# AD_0.net
KiCad netlist of a schematic drawn in Altium Designer
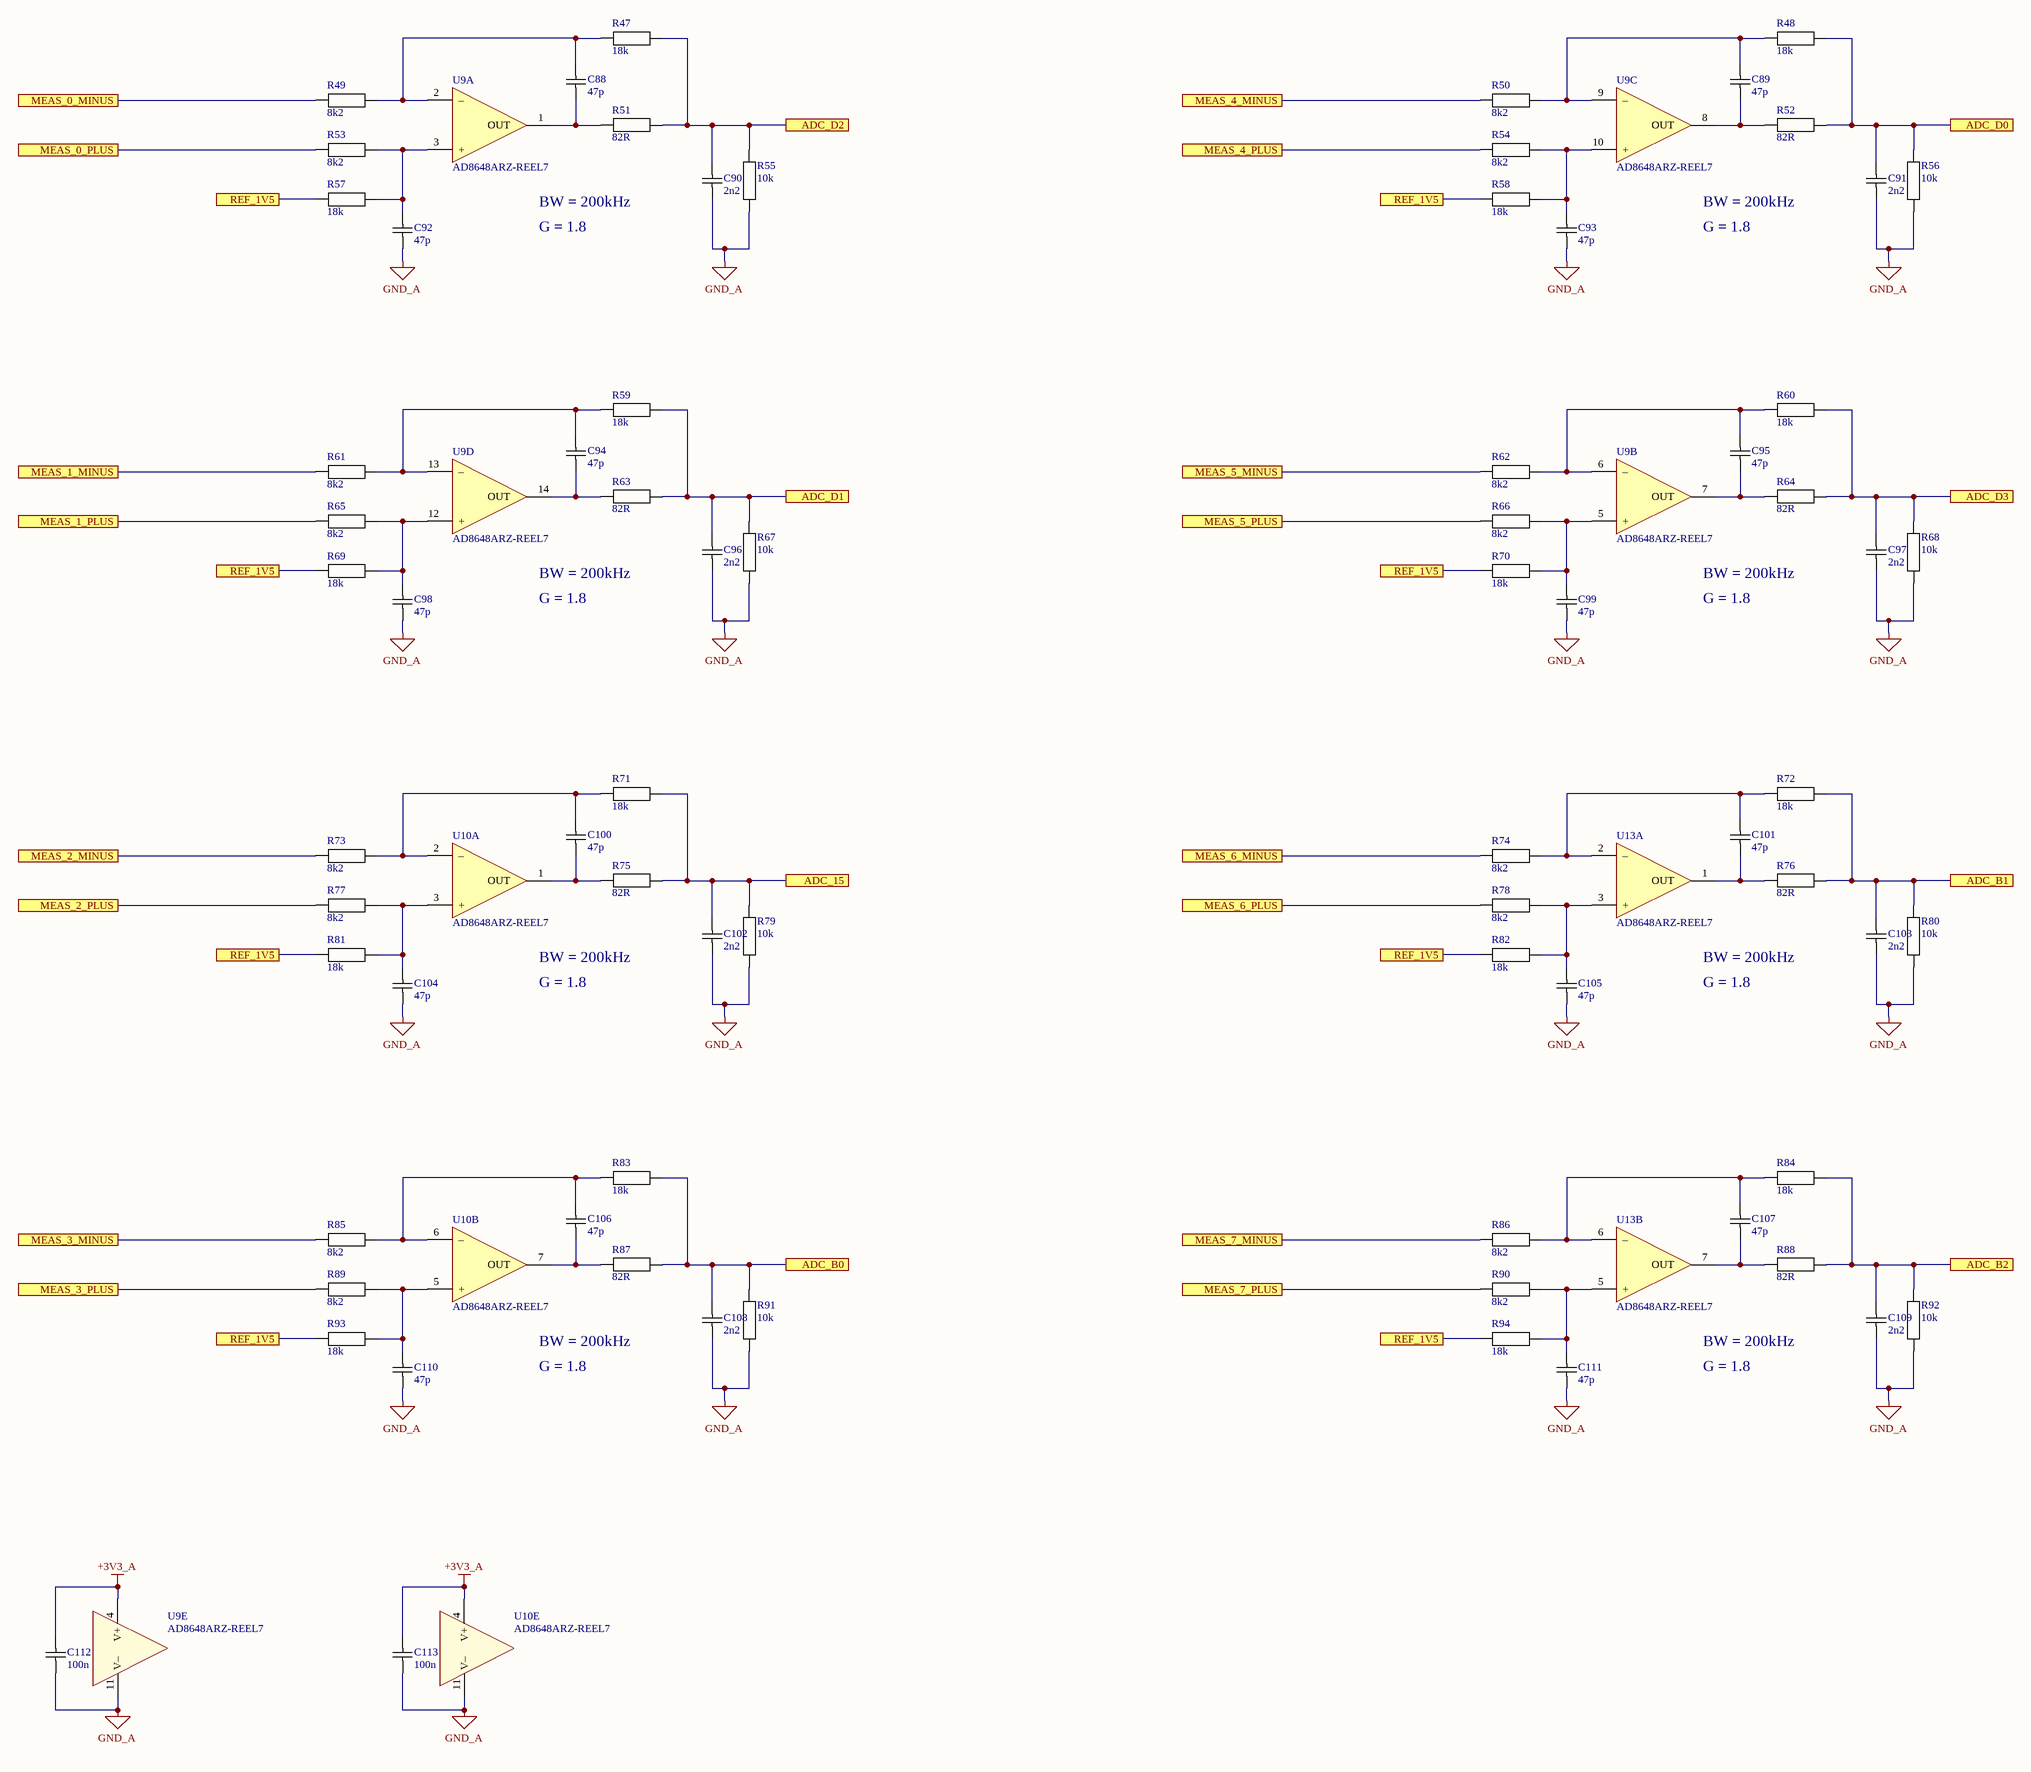
[diagram p0: AD_0.SchDoc]

(export (version "E")
  (design (tool "Eeschema 10.0.6"))
  (components
    (comp (ref "C88")
      (value "47p")
      (footprint "CAPACITOR 1608 REFLOW")
      (description "Capacitor X7R 10% 50V 1608(0603)")
      (libsource (lib "Capacitor") (part "Capacitor"))
    )
    (comp (ref "C89")
      (value "47p")
      (footprint "CAPACITOR 1608 REFLOW")
      (description "Capacitor X7R 10% 50V 1608(0603)")
      (libsource (lib "Capacitor") (part "Capacitor"))
    )
    (comp (ref "C90")
      (value "2n2")
      (footprint "CAPACITOR 1608 REFLOW")
      (description "Capacitor X7R 10% 50V 1608(0603)")
      (libsource (lib "Capacitor") (part "Capacitor"))
    )
    (comp (ref "C91")
      (value "2n2")
      (footprint "CAPACITOR 1608 REFLOW")
      (description "Capacitor X7R 10% 50V 1608(0603)")
      (libsource (lib "Capacitor") (part "Capacitor"))
    )
    (comp (ref "C92")
      (value "47p")
      (footprint "CAPACITOR 1608 REFLOW")
      (description "Capacitor X7R 10% 50V 1608(0603)")
      (libsource (lib "Capacitor") (part "Capacitor"))
    )
    (comp (ref "C93")
      (value "47p")
      (footprint "CAPACITOR 1608 REFLOW")
      (description "Capacitor X7R 10% 50V 1608(0603)")
      (libsource (lib "Capacitor") (part "Capacitor"))
    )
    (comp (ref "C94")
      (value "47p")
      (footprint "CAPACITOR 1608 REFLOW")
      (description "Capacitor X7R 10% 50V 1608(0603)")
      (libsource (lib "Capacitor") (part "Capacitor"))
    )
    (comp (ref "C95")
      (value "47p")
      (footprint "CAPACITOR 1608 REFLOW")
      (description "Capacitor X7R 10% 50V 1608(0603)")
      (libsource (lib "Capacitor") (part "Capacitor"))
    )
    (comp (ref "C96")
      (value "2n2")
      (footprint "CAPACITOR 1608 REFLOW")
      (description "Capacitor X7R 10% 50V 1608(0603)")
      (libsource (lib "Capacitor") (part "Capacitor"))
    )
    (comp (ref "C97")
      (value "2n2")
      (footprint "CAPACITOR 1608 REFLOW")
      (description "Capacitor X7R 10% 50V 1608(0603)")
      (libsource (lib "Capacitor") (part "Capacitor"))
    )
    (comp (ref "C98")
      (value "47p")
      (footprint "CAPACITOR 1608 REFLOW")
      (description "Capacitor X7R 10% 50V 1608(0603)")
      (libsource (lib "Capacitor") (part "Capacitor"))
    )
    (comp (ref "C99")
      (value "47p")
      (footprint "CAPACITOR 1608 REFLOW")
      (description "Capacitor X7R 10% 50V 1608(0603)")
      (libsource (lib "Capacitor") (part "Capacitor"))
    )
    (comp (ref "C100")
      (value "47p")
      (footprint "CAPACITOR 1608 REFLOW")
      (description "Capacitor X7R 10% 50V 1608(0603)")
      (libsource (lib "Capacitor") (part "Capacitor"))
    )
    (comp (ref "C101")
      (value "47p")
      (footprint "CAPACITOR 1608 REFLOW")
      (description "Capacitor X7R 10% 50V 1608(0603)")
      (libsource (lib "Capacitor") (part "Capacitor"))
    )
    (comp (ref "C102")
      (value "2n2")
      (footprint "CAPACITOR 1608 REFLOW")
      (description "Capacitor X7R 10% 50V 1608(0603)")
      (libsource (lib "Capacitor") (part "Capacitor"))
    )
    (comp (ref "C103")
      (value "2n2")
      (footprint "CAPACITOR 1608 REFLOW")
      (description "Capacitor X7R 10% 50V 1608(0603)")
      (libsource (lib "Capacitor") (part "Capacitor"))
    )
    (comp (ref "C104")
      (value "47p")
      (footprint "CAPACITOR 1608 REFLOW")
      (description "Capacitor X7R 10% 50V 1608(0603)")
      (libsource (lib "Capacitor") (part "Capacitor"))
    )
    (comp (ref "C105")
      (value "47p")
      (footprint "CAPACITOR 1608 REFLOW")
      (description "Capacitor X7R 10% 50V 1608(0603)")
      (libsource (lib "Capacitor") (part "Capacitor"))
    )
    (comp (ref "C106")
      (value "47p")
      (footprint "CAPACITOR 1608 REFLOW")
      (description "Capacitor X7R 10% 50V 1608(0603)")
      (libsource (lib "Capacitor") (part "Capacitor"))
    )
    (comp (ref "C107")
      (value "47p")
      (footprint "CAPACITOR 1608 REFLOW")
      (description "Capacitor X7R 10% 50V 1608(0603)")
      (libsource (lib "Capacitor") (part "Capacitor"))
    )
    (comp (ref "C108")
      (value "2n2")
      (footprint "CAPACITOR 1608 REFLOW")
      (description "Capacitor X7R 10% 50V 1608(0603)")
      (libsource (lib "Capacitor") (part "Capacitor"))
    )
    (comp (ref "C109")
      (value "2n2")
      (footprint "CAPACITOR 1608 REFLOW")
      (description "Capacitor X7R 10% 50V 1608(0603)")
      (libsource (lib "Capacitor") (part "Capacitor"))
    )
    (comp (ref "C110")
      (value "47p")
      (footprint "CAPACITOR 1608 REFLOW")
      (description "Capacitor X7R 10% 50V 1608(0603)")
      (libsource (lib "Capacitor") (part "Capacitor"))
    )
    (comp (ref "C111")
      (value "47p")
      (footprint "CAPACITOR 1608 REFLOW")
      (description "Capacitor X7R 10% 50V 1608(0603)")
      (libsource (lib "Capacitor") (part "Capacitor"))
    )
    (comp (ref "C112")
      (value "100n")
      (footprint "CAPACITOR 1608 REFLOW")
      (description "Capacitor X7R 10% 50V 1608(0603)")
      (libsource (lib "Capacitor") (part "Capacitor"))
    )
    (comp (ref "C113")
      (value "100n")
      (footprint "CAPACITOR 1608 REFLOW")
      (description "Capacitor X7R 10% 50V 1608(0603)")
      (libsource (lib "Capacitor") (part "Capacitor"))
    )
    (comp (ref "R47")
      (value "18k")
      (footprint "RESISTOR 1608 REFLOW")
      (description "Resistor 1% 50V 100mW 1608(0603)")
      (libsource (lib "Resistor") (part "Resistor"))
    )
    (comp (ref "R48")
      (value "18k")
      (footprint "RESISTOR 1608 REFLOW")
      (description "Resistor 1% 50V 100mW 1608(0603)")
      (libsource (lib "Resistor") (part "Resistor"))
    )
    (comp (ref "R49")
      (value "8k2")
      (footprint "RESISTOR 1608 REFLOW")
      (description "Resistor 1% 50V 100mW 1608(0603)")
      (libsource (lib "Resistor") (part "Resistor"))
    )
    (comp (ref "R50")
      (value "8k2")
      (footprint "RESISTOR 1608 REFLOW")
      (description "Resistor 1% 50V 100mW 1608(0603)")
      (libsource (lib "Resistor") (part "Resistor"))
    )
    (comp (ref "R51")
      (value "82R")
      (footprint "RESISTOR 1608 REFLOW")
      (description "Resistor 1% 50V 100mW 1608(0603)")
      (libsource (lib "Resistor") (part "Resistor"))
    )
    (comp (ref "R52")
      (value "82R")
      (footprint "RESISTOR 1608 REFLOW")
      (description "Resistor 1% 50V 100mW 1608(0603)")
      (libsource (lib "Resistor") (part "Resistor"))
    )
    (comp (ref "R53")
      (value "8k2")
      (footprint "RESISTOR 1608 REFLOW")
      (description "Resistor 1% 50V 100mW 1608(0603)")
      (libsource (lib "Resistor") (part "Resistor"))
    )
    (comp (ref "R54")
      (value "8k2")
      (footprint "RESISTOR 1608 REFLOW")
      (description "Resistor 1% 50V 100mW 1608(0603)")
      (libsource (lib "Resistor") (part "Resistor"))
    )
    (comp (ref "R55")
      (value "10k")
      (footprint "RESISTOR 1608 REFLOW")
      (description "Resistor 1% 50V 100mW 1608(0603)")
      (libsource (lib "Resistor") (part "Resistor"))
    )
    (comp (ref "R56")
      (value "10k")
      (footprint "RESISTOR 1608 REFLOW")
      (description "Resistor 1% 50V 100mW 1608(0603)")
      (libsource (lib "Resistor") (part "Resistor"))
    )
    (comp (ref "R57")
      (value "18k")
      (footprint "RESISTOR 1608 REFLOW")
      (description "Resistor 1% 50V 100mW 1608(0603)")
      (libsource (lib "Resistor") (part "Resistor"))
    )
    (comp (ref "R58")
      (value "18k")
      (footprint "RESISTOR 1608 REFLOW")
      (description "Resistor 1% 50V 100mW 1608(0603)")
      (libsource (lib "Resistor") (part "Resistor"))
    )
    (comp (ref "R59")
      (value "18k")
      (footprint "RESISTOR 1608 REFLOW")
      (description "Resistor 1% 50V 100mW 1608(0603)")
      (libsource (lib "Resistor") (part "Resistor"))
    )
    (comp (ref "R60")
      (value "18k")
      (footprint "RESISTOR 1608 REFLOW")
      (description "Resistor 1% 50V 100mW 1608(0603)")
      (libsource (lib "Resistor") (part "Resistor"))
    )
    (comp (ref "R61")
      (value "8k2")
      (footprint "RESISTOR 1608 REFLOW")
      (description "Resistor 1% 50V 100mW 1608(0603)")
      (libsource (lib "Resistor") (part "Resistor"))
    )
    (comp (ref "R62")
      (value "8k2")
      (footprint "RESISTOR 1608 REFLOW")
      (description "Resistor 1% 50V 100mW 1608(0603)")
      (libsource (lib "Resistor") (part "Resistor"))
    )
    (comp (ref "R63")
      (value "82R")
      (footprint "RESISTOR 1608 REFLOW")
      (description "Resistor 1% 50V 100mW 1608(0603)")
      (libsource (lib "Resistor") (part "Resistor"))
    )
    (comp (ref "R64")
      (value "82R")
      (footprint "RESISTOR 1608 REFLOW")
      (description "Resistor 1% 50V 100mW 1608(0603)")
      (libsource (lib "Resistor") (part "Resistor"))
    )
    (comp (ref "R65")
      (value "8k2")
      (footprint "RESISTOR 1608 REFLOW")
      (description "Resistor 1% 50V 100mW 1608(0603)")
      (libsource (lib "Resistor") (part "Resistor"))
    )
    (comp (ref "R66")
      (value "8k2")
      (footprint "RESISTOR 1608 REFLOW")
      (description "Resistor 1% 50V 100mW 1608(0603)")
      (libsource (lib "Resistor") (part "Resistor"))
    )
    (comp (ref "R67")
      (value "10k")
      (footprint "RESISTOR 1608 REFLOW")
      (description "Resistor 1% 50V 100mW 1608(0603)")
      (libsource (lib "Resistor") (part "Resistor"))
    )
    (comp (ref "R68")
      (value "10k")
      (footprint "RESISTOR 1608 REFLOW")
      (description "Resistor 1% 50V 100mW 1608(0603)")
      (libsource (lib "Resistor") (part "Resistor"))
    )
    (comp (ref "R69")
      (value "18k")
      (footprint "RESISTOR 1608 REFLOW")
      (description "Resistor 1% 50V 100mW 1608(0603)")
      (libsource (lib "Resistor") (part "Resistor"))
    )
    (comp (ref "R70")
      (value "18k")
      (footprint "RESISTOR 1608 REFLOW")
      (description "Resistor 1% 50V 100mW 1608(0603)")
      (libsource (lib "Resistor") (part "Resistor"))
    )
    (comp (ref "R71")
      (value "18k")
      (footprint "RESISTOR 1608 REFLOW")
      (description "Resistor 1% 50V 100mW 1608(0603)")
      (libsource (lib "Resistor") (part "Resistor"))
    )
    (comp (ref "R72")
      (value "18k")
      (footprint "RESISTOR 1608 REFLOW")
      (description "Resistor 1% 50V 100mW 1608(0603)")
      (libsource (lib "Resistor") (part "Resistor"))
    )
    (comp (ref "R73")
      (value "8k2")
      (footprint "RESISTOR 1608 REFLOW")
      (description "Resistor 1% 50V 100mW 1608(0603)")
      (libsource (lib "Resistor") (part "Resistor"))
    )
    (comp (ref "R74")
      (value "8k2")
      (footprint "RESISTOR 1608 REFLOW")
      (description "Resistor 1% 50V 100mW 1608(0603)")
      (libsource (lib "Resistor") (part "Resistor"))
    )
    (comp (ref "R75")
      (value "82R")
      (footprint "RESISTOR 1608 REFLOW")
      (description "Resistor 1% 50V 100mW 1608(0603)")
      (libsource (lib "Resistor") (part "Resistor"))
    )
    (comp (ref "R76")
      (value "82R")
      (footprint "RESISTOR 1608 REFLOW")
      (description "Resistor 1% 50V 100mW 1608(0603)")
      (libsource (lib "Resistor") (part "Resistor"))
    )
    (comp (ref "R77")
      (value "8k2")
      (footprint "RESISTOR 1608 REFLOW")
      (description "Resistor 1% 50V 100mW 1608(0603)")
      (libsource (lib "Resistor") (part "Resistor"))
    )
    (comp (ref "R78")
      (value "8k2")
      (footprint "RESISTOR 1608 REFLOW")
      (description "Resistor 1% 50V 100mW 1608(0603)")
      (libsource (lib "Resistor") (part "Resistor"))
    )
    (comp (ref "R79")
      (value "10k")
      (footprint "RESISTOR 1608 REFLOW")
      (description "Resistor 1% 50V 100mW 1608(0603)")
      (libsource (lib "Resistor") (part "Resistor"))
    )
    (comp (ref "R80")
      (value "10k")
      (footprint "RESISTOR 1608 REFLOW")
      (description "Resistor 1% 50V 100mW 1608(0603)")
      (libsource (lib "Resistor") (part "Resistor"))
    )
    (comp (ref "R81")
      (value "18k")
      (footprint "RESISTOR 1608 REFLOW")
      (description "Resistor 1% 50V 100mW 1608(0603)")
      (libsource (lib "Resistor") (part "Resistor"))
    )
    (comp (ref "R82")
      (value "18k")
      (footprint "RESISTOR 1608 REFLOW")
      (description "Resistor 1% 50V 100mW 1608(0603)")
      (libsource (lib "Resistor") (part "Resistor"))
    )
    (comp (ref "R83")
      (value "18k")
      (footprint "RESISTOR 1608 REFLOW")
      (description "Resistor 1% 50V 100mW 1608(0603)")
      (libsource (lib "Resistor") (part "Resistor"))
    )
    (comp (ref "R84")
      (value "18k")
      (footprint "RESISTOR 1608 REFLOW")
      (description "Resistor 1% 50V 100mW 1608(0603)")
      (libsource (lib "Resistor") (part "Resistor"))
    )
    (comp (ref "R85")
      (value "8k2")
      (footprint "RESISTOR 1608 REFLOW")
      (description "Resistor 1% 50V 100mW 1608(0603)")
      (libsource (lib "Resistor") (part "Resistor"))
    )
    (comp (ref "R86")
      (value "8k2")
      (footprint "RESISTOR 1608 REFLOW")
      (description "Resistor 1% 50V 100mW 1608(0603)")
      (libsource (lib "Resistor") (part "Resistor"))
    )
    (comp (ref "R87")
      (value "82R")
      (footprint "RESISTOR 1608 REFLOW")
      (description "Resistor 1% 50V 100mW 1608(0603)")
      (libsource (lib "Resistor") (part "Resistor"))
    )
    (comp (ref "R88")
      (value "82R")
      (footprint "RESISTOR 1608 REFLOW")
      (description "Resistor 1% 50V 100mW 1608(0603)")
      (libsource (lib "Resistor") (part "Resistor"))
    )
    (comp (ref "R89")
      (value "8k2")
      (footprint "RESISTOR 1608 REFLOW")
      (description "Resistor 1% 50V 100mW 1608(0603)")
      (libsource (lib "Resistor") (part "Resistor"))
    )
    (comp (ref "R90")
      (value "8k2")
      (footprint "RESISTOR 1608 REFLOW")
      (description "Resistor 1% 50V 100mW 1608(0603)")
      (libsource (lib "Resistor") (part "Resistor"))
    )
    (comp (ref "R91")
      (value "10k")
      (footprint "RESISTOR 1608 REFLOW")
      (description "Resistor 1% 50V 100mW 1608(0603)")
      (libsource (lib "Resistor") (part "Resistor"))
    )
    (comp (ref "R92")
      (value "10k")
      (footprint "RESISTOR 1608 REFLOW")
      (description "Resistor 1% 50V 100mW 1608(0603)")
      (libsource (lib "Resistor") (part "Resistor"))
    )
    (comp (ref "R93")
      (value "18k")
      (footprint "RESISTOR 1608 REFLOW")
      (description "Resistor 1% 50V 100mW 1608(0603)")
      (libsource (lib "Resistor") (part "Resistor"))
    )
    (comp (ref "R94")
      (value "18k")
      (footprint "RESISTOR 1608 REFLOW")
      (description "Resistor 1% 50V 100mW 1608(0603)")
      (libsource (lib "Resistor") (part "Resistor"))
    )
    (comp (ref "U9")
      (value "AD8648ARZ-REEL7")
      (footprint "SO14 P1.27 C4.0X8.8 H1.75")
      (description "Generic quad OPA 14 pins")
      (fields (field (name "MANUFACTURER") "Analog Devices"))
      (libsource (lib "Amplifier") (part "OPA QUAD"))
    )
    (comp (ref "U10")
      (value "AD8648ARZ-REEL7")
      (footprint "SO14 P1.27 C4.0X8.8 H1.75")
      (description "Generic quad OPA 14 pins")
      (fields (field (name "MANUFACTURER") "Analog Devices"))
      (libsource (lib "Amplifier") (part "OPA QUAD"))
    )
    (comp (ref "U13")
      (value "AD8648ARZ-REEL7")
      (footprint "SO14 P1.27 C4.0X8.8 H1.75")
      (description "Generic quad OPA 14 pins")
      (fields (field (name "MANUFACTURER") "Analog Devices"))
      (libsource (lib "Amplifier") (part "OPA QUAD"))
    )
  )
  (nets
    (net (code "1") (name "+3V3_A") (class "Default")
      (node (ref "C112") (pin "2") (pinfunction "2_2") (pintype "passive"))
      (node (ref "C113") (pin "2") (pinfunction "2_2") (pintype "passive"))
      (node (ref "U10") (pin "4") (pinfunction "V+_4") (pintype "passive"))
      (node (ref "U9") (pin "4") (pinfunction "V+_4") (pintype "passive"))
    )
    (net (code "2") (name "/ADC_15") (class "Default")
      (node (ref "C102") (pin "2") (pinfunction "2_2") (pintype "passive"))
      (node (ref "R71") (pin "2") (pinfunction "2_2") (pintype "passive"))
      (node (ref "R75") (pin "2") (pinfunction "2_2") (pintype "passive"))
      (node (ref "R79") (pin "1") (pinfunction "1_1") (pintype "passive"))
    )
    (net (code "3") (name "/ADC_B0") (class "Default")
      (node (ref "C108") (pin "2") (pinfunction "2_2") (pintype "passive"))
      (node (ref "R83") (pin "2") (pinfunction "2_2") (pintype "passive"))
      (node (ref "R87") (pin "2") (pinfunction "2_2") (pintype "passive"))
      (node (ref "R91") (pin "1") (pinfunction "1_1") (pintype "passive"))
    )
    (net (code "4") (name "/ADC_B1") (class "Default")
      (node (ref "C103") (pin "2") (pinfunction "2_2") (pintype "passive"))
      (node (ref "R72") (pin "2") (pinfunction "2_2") (pintype "passive"))
      (node (ref "R76") (pin "2") (pinfunction "2_2") (pintype "passive"))
      (node (ref "R80") (pin "1") (pinfunction "1_1") (pintype "passive"))
    )
    (net (code "5") (name "/ADC_B2") (class "Default")
      (node (ref "C109") (pin "2") (pinfunction "2_2") (pintype "passive"))
      (node (ref "R84") (pin "2") (pinfunction "2_2") (pintype "passive"))
      (node (ref "R88") (pin "2") (pinfunction "2_2") (pintype "passive"))
      (node (ref "R92") (pin "1") (pinfunction "1_1") (pintype "passive"))
    )
    (net (code "6") (name "/ADC_D0") (class "Default")
      (node (ref "C91") (pin "2") (pinfunction "2_2") (pintype "passive"))
      (node (ref "R48") (pin "2") (pinfunction "2_2") (pintype "passive"))
      (node (ref "R52") (pin "2") (pinfunction "2_2") (pintype "passive"))
      (node (ref "R56") (pin "1") (pinfunction "1_1") (pintype "passive"))
    )
    (net (code "7") (name "/ADC_D1") (class "Default")
      (node (ref "C96") (pin "2") (pinfunction "2_2") (pintype "passive"))
      (node (ref "R59") (pin "2") (pinfunction "2_2") (pintype "passive"))
      (node (ref "R63") (pin "2") (pinfunction "2_2") (pintype "passive"))
      (node (ref "R67") (pin "1") (pinfunction "1_1") (pintype "passive"))
    )
    (net (code "8") (name "/ADC_D2") (class "Default")
      (node (ref "C90") (pin "2") (pinfunction "2_2") (pintype "passive"))
      (node (ref "R47") (pin "2") (pinfunction "2_2") (pintype "passive"))
      (node (ref "R51") (pin "2") (pinfunction "2_2") (pintype "passive"))
      (node (ref "R55") (pin "1") (pinfunction "1_1") (pintype "passive"))
    )
    (net (code "9") (name "/ADC_D3") (class "Default")
      (node (ref "C97") (pin "2") (pinfunction "2_2") (pintype "passive"))
      (node (ref "R60") (pin "2") (pinfunction "2_2") (pintype "passive"))
      (node (ref "R64") (pin "2") (pinfunction "2_2") (pintype "passive"))
      (node (ref "R68") (pin "1") (pinfunction "1_1") (pintype "passive"))
    )
    (net (code "10") (name "/MEAS_0_MINUS") (class "Default")
      (node (ref "R49") (pin "1") (pinfunction "1_1") (pintype "passive"))
    )
    (net (code "11") (name "/MEAS_0_PLUS") (class "Default")
      (node (ref "R53") (pin "1") (pinfunction "1_1") (pintype "passive"))
    )
    (net (code "12") (name "/MEAS_1_MINUS") (class "Default")
      (node (ref "R61") (pin "1") (pinfunction "1_1") (pintype "passive"))
    )
    (net (code "13") (name "/MEAS_1_PLUS") (class "Default")
      (node (ref "R65") (pin "1") (pinfunction "1_1") (pintype "passive"))
    )
    (net (code "14") (name "/MEAS_2_MINUS") (class "Default")
      (node (ref "R73") (pin "1") (pinfunction "1_1") (pintype "passive"))
    )
    (net (code "15") (name "/MEAS_2_PLUS") (class "Default")
      (node (ref "R77") (pin "1") (pinfunction "1_1") (pintype "passive"))
    )
    (net (code "16") (name "/MEAS_3_MINUS") (class "Default")
      (node (ref "R85") (pin "1") (pinfunction "1_1") (pintype "passive"))
    )
    (net (code "17") (name "/MEAS_3_PLUS") (class "Default")
      (node (ref "R89") (pin "1") (pinfunction "1_1") (pintype "passive"))
    )
    (net (code "18") (name "/MEAS_4_MINUS") (class "Default")
      (node (ref "R50") (pin "1") (pinfunction "1_1") (pintype "passive"))
    )
    (net (code "19") (name "/MEAS_4_PLUS") (class "Default")
      (node (ref "R54") (pin "1") (pinfunction "1_1") (pintype "passive"))
    )
    (net (code "20") (name "/MEAS_5_MINUS") (class "Default")
      (node (ref "R62") (pin "1") (pinfunction "1_1") (pintype "passive"))
    )
    (net (code "21") (name "/MEAS_5_PLUS") (class "Default")
      (node (ref "R66") (pin "1") (pinfunction "1_1") (pintype "passive"))
    )
    (net (code "22") (name "/MEAS_6_MINUS") (class "Default")
      (node (ref "R74") (pin "1") (pinfunction "1_1") (pintype "passive"))
    )
    (net (code "23") (name "/MEAS_6_PLUS") (class "Default")
      (node (ref "R78") (pin "1") (pinfunction "1_1") (pintype "passive"))
    )
    (net (code "24") (name "/MEAS_7_MINUS") (class "Default")
      (node (ref "R86") (pin "1") (pinfunction "1_1") (pintype "passive"))
    )
    (net (code "25") (name "/MEAS_7_PLUS") (class "Default")
      (node (ref "R90") (pin "1") (pinfunction "1_1") (pintype "passive"))
    )
    (net (code "26") (name "/REF_1V5") (class "Default")
      (node (ref "R57") (pin "2") (pinfunction "2_2") (pintype "passive"))
      (node (ref "R58") (pin "2") (pinfunction "2_2") (pintype "passive"))
      (node (ref "R69") (pin "2") (pinfunction "2_2") (pintype "passive"))
      (node (ref "R70") (pin "2") (pinfunction "2_2") (pintype "passive"))
      (node (ref "R81") (pin "2") (pinfunction "2_2") (pintype "passive"))
      (node (ref "R82") (pin "2") (pinfunction "2_2") (pintype "passive"))
      (node (ref "R93") (pin "2") (pinfunction "2_2") (pintype "passive"))
      (node (ref "R94") (pin "2") (pinfunction "2_2") (pintype "passive"))
    )
    (net (code "27") (name "GND_A") (class "Default")
      (node (ref "C102") (pin "1") (pinfunction "1_1") (pintype "passive"))
      (node (ref "C103") (pin "1") (pinfunction "1_1") (pintype "passive"))
      (node (ref "C104") (pin "1") (pinfunction "1_1") (pintype "passive"))
      (node (ref "C105") (pin "1") (pinfunction "1_1") (pintype "passive"))
      (node (ref "C108") (pin "1") (pinfunction "1_1") (pintype "passive"))
      (node (ref "C109") (pin "1") (pinfunction "1_1") (pintype "passive"))
      (node (ref "C110") (pin "1") (pinfunction "1_1") (pintype "passive"))
      (node (ref "C111") (pin "1") (pinfunction "1_1") (pintype "passive"))
      (node (ref "C112") (pin "1") (pinfunction "1_1") (pintype "passive"))
      (node (ref "C113") (pin "1") (pinfunction "1_1") (pintype "passive"))
      (node (ref "C90") (pin "1") (pinfunction "1_1") (pintype "passive"))
      (node (ref "C91") (pin "1") (pinfunction "1_1") (pintype "passive"))
      (node (ref "C92") (pin "1") (pinfunction "1_1") (pintype "passive"))
      (node (ref "C93") (pin "1") (pinfunction "1_1") (pintype "passive"))
      (node (ref "C96") (pin "1") (pinfunction "1_1") (pintype "passive"))
      (node (ref "C97") (pin "1") (pinfunction "1_1") (pintype "passive"))
      (node (ref "C98") (pin "1") (pinfunction "1_1") (pintype "passive"))
      (node (ref "C99") (pin "1") (pinfunction "1_1") (pintype "passive"))
      (node (ref "R55") (pin "2") (pinfunction "2_2") (pintype "passive"))
      (node (ref "R56") (pin "2") (pinfunction "2_2") (pintype "passive"))
      (node (ref "R67") (pin "2") (pinfunction "2_2") (pintype "passive"))
      (node (ref "R68") (pin "2") (pinfunction "2_2") (pintype "passive"))
      (node (ref "R79") (pin "2") (pinfunction "2_2") (pintype "passive"))
      (node (ref "R80") (pin "2") (pinfunction "2_2") (pintype "passive"))
      (node (ref "R91") (pin "2") (pinfunction "2_2") (pintype "passive"))
      (node (ref "R92") (pin "2") (pinfunction "2_2") (pintype "passive"))
      (node (ref "U10") (pin "11") (pinfunction "V–_11") (pintype "passive"))
      (node (ref "U9") (pin "11") (pinfunction "V–_11") (pintype "passive"))
    )
    (net (code "28") (name "Net-(U9A-+)") (class "Default")
      (node (ref "C92") (pin "2") (pinfunction "2_2") (pintype "passive"))
      (node (ref "R53") (pin "2") (pinfunction "2_2") (pintype "passive"))
      (node (ref "R57") (pin "1") (pinfunction "1_1") (pintype "passive"))
      (node (ref "U9") (pin "3") (pinfunction "+_3") (pintype "passive"))
    )
    (net (code "29") (name "Net-(U9A-OUT)") (class "Default")
      (node (ref "C88") (pin "1") (pinfunction "1_1") (pintype "passive"))
      (node (ref "R51") (pin "1") (pinfunction "1_1") (pintype "passive"))
      (node (ref "U9") (pin "1") (pinfunction "OUT_1") (pintype "passive"))
    )
    (net (code "30") (name "Net-(U9A-–)") (class "Default")
      (node (ref "C88") (pin "2") (pinfunction "2_2") (pintype "passive"))
      (node (ref "R47") (pin "1") (pinfunction "1_1") (pintype "passive"))
      (node (ref "R49") (pin "2") (pinfunction "2_2") (pintype "passive"))
      (node (ref "U9") (pin "2") (pinfunction "–_2") (pintype "passive"))
    )
    (net (code "31") (name "Net-(U9B-+)") (class "Default")
      (node (ref "C99") (pin "2") (pinfunction "2_2") (pintype "passive"))
      (node (ref "R66") (pin "2") (pinfunction "2_2") (pintype "passive"))
      (node (ref "R70") (pin "1") (pinfunction "1_1") (pintype "passive"))
      (node (ref "U9") (pin "5") (pinfunction "+_5") (pintype "passive"))
    )
    (net (code "32") (name "Net-(U9B-OUT)") (class "Default")
      (node (ref "C95") (pin "1") (pinfunction "1_1") (pintype "passive"))
      (node (ref "R64") (pin "1") (pinfunction "1_1") (pintype "passive"))
      (node (ref "U9") (pin "7") (pinfunction "OUT_7") (pintype "passive"))
    )
    (net (code "33") (name "Net-(U9B-–)") (class "Default")
      (node (ref "C95") (pin "2") (pinfunction "2_2") (pintype "passive"))
      (node (ref "R60") (pin "1") (pinfunction "1_1") (pintype "passive"))
      (node (ref "R62") (pin "2") (pinfunction "2_2") (pintype "passive"))
      (node (ref "U9") (pin "6") (pinfunction "–_6") (pintype "passive"))
    )
    (net (code "34") (name "Net-(U9C-+)") (class "Default")
      (node (ref "C93") (pin "2") (pinfunction "2_2") (pintype "passive"))
      (node (ref "R54") (pin "2") (pinfunction "2_2") (pintype "passive"))
      (node (ref "R58") (pin "1") (pinfunction "1_1") (pintype "passive"))
      (node (ref "U9") (pin "10") (pinfunction "+_10") (pintype "passive"))
    )
    (net (code "35") (name "Net-(U9C-OUT)") (class "Default")
      (node (ref "C89") (pin "1") (pinfunction "1_1") (pintype "passive"))
      (node (ref "R52") (pin "1") (pinfunction "1_1") (pintype "passive"))
      (node (ref "U9") (pin "8") (pinfunction "OUT_8") (pintype "passive"))
    )
    (net (code "36") (name "Net-(U9C-–)") (class "Default")
      (node (ref "C89") (pin "2") (pinfunction "2_2") (pintype "passive"))
      (node (ref "R48") (pin "1") (pinfunction "1_1") (pintype "passive"))
      (node (ref "R50") (pin "2") (pinfunction "2_2") (pintype "passive"))
      (node (ref "U9") (pin "9") (pinfunction "–_9") (pintype "passive"))
    )
    (net (code "37") (name "Net-(U9D-+)") (class "Default")
      (node (ref "C98") (pin "2") (pinfunction "2_2") (pintype "passive"))
      (node (ref "R65") (pin "2") (pinfunction "2_2") (pintype "passive"))
      (node (ref "R69") (pin "1") (pinfunction "1_1") (pintype "passive"))
      (node (ref "U9") (pin "12") (pinfunction "+_12") (pintype "passive"))
    )
    (net (code "38") (name "Net-(U9D-OUT)") (class "Default")
      (node (ref "C94") (pin "1") (pinfunction "1_1") (pintype "passive"))
      (node (ref "R63") (pin "1") (pinfunction "1_1") (pintype "passive"))
      (node (ref "U9") (pin "14") (pinfunction "OUT_14") (pintype "passive"))
    )
    (net (code "39") (name "Net-(U9D-–)") (class "Default")
      (node (ref "C94") (pin "2") (pinfunction "2_2") (pintype "passive"))
      (node (ref "R59") (pin "1") (pinfunction "1_1") (pintype "passive"))
      (node (ref "R61") (pin "2") (pinfunction "2_2") (pintype "passive"))
      (node (ref "U9") (pin "13") (pinfunction "–_13") (pintype "passive"))
    )
    (net (code "40") (name "Net-(U10A-+)") (class "Default")
      (node (ref "C104") (pin "2") (pinfunction "2_2") (pintype "passive"))
      (node (ref "R77") (pin "2") (pinfunction "2_2") (pintype "passive"))
      (node (ref "R81") (pin "1") (pinfunction "1_1") (pintype "passive"))
      (node (ref "U10") (pin "3") (pinfunction "+_3") (pintype "passive"))
    )
    (net (code "41") (name "Net-(U10A-OUT)") (class "Default")
      (node (ref "C100") (pin "1") (pinfunction "1_1") (pintype "passive"))
      (node (ref "R75") (pin "1") (pinfunction "1_1") (pintype "passive"))
      (node (ref "U10") (pin "1") (pinfunction "OUT_1") (pintype "passive"))
    )
    (net (code "42") (name "Net-(U10A-–)") (class "Default")
      (node (ref "C100") (pin "2") (pinfunction "2_2") (pintype "passive"))
      (node (ref "R71") (pin "1") (pinfunction "1_1") (pintype "passive"))
      (node (ref "R73") (pin "2") (pinfunction "2_2") (pintype "passive"))
      (node (ref "U10") (pin "2") (pinfunction "–_2") (pintype "passive"))
    )
    (net (code "43") (name "Net-(U10B-+)") (class "Default")
      (node (ref "C110") (pin "2") (pinfunction "2_2") (pintype "passive"))
      (node (ref "R89") (pin "2") (pinfunction "2_2") (pintype "passive"))
      (node (ref "R93") (pin "1") (pinfunction "1_1") (pintype "passive"))
      (node (ref "U10") (pin "5") (pinfunction "+_5") (pintype "passive"))
    )
    (net (code "44") (name "Net-(U10B-OUT)") (class "Default")
      (node (ref "C106") (pin "1") (pinfunction "1_1") (pintype "passive"))
      (node (ref "R87") (pin "1") (pinfunction "1_1") (pintype "passive"))
      (node (ref "U10") (pin "7") (pinfunction "OUT_7") (pintype "passive"))
    )
    (net (code "45") (name "Net-(U10B-–)") (class "Default")
      (node (ref "C106") (pin "2") (pinfunction "2_2") (pintype "passive"))
      (node (ref "R83") (pin "1") (pinfunction "1_1") (pintype "passive"))
      (node (ref "R85") (pin "2") (pinfunction "2_2") (pintype "passive"))
      (node (ref "U10") (pin "6") (pinfunction "–_6") (pintype "passive"))
    )
    (net (code "46") (name "Net-(U13A-+)") (class "Default")
      (node (ref "C105") (pin "2") (pinfunction "2_2") (pintype "passive"))
      (node (ref "R78") (pin "2") (pinfunction "2_2") (pintype "passive"))
      (node (ref "R82") (pin "1") (pinfunction "1_1") (pintype "passive"))
      (node (ref "U13") (pin "3") (pinfunction "+_3") (pintype "passive"))
    )
    (net (code "47") (name "Net-(U13A-OUT)") (class "Default")
      (node (ref "C101") (pin "1") (pinfunction "1_1") (pintype "passive"))
      (node (ref "R76") (pin "1") (pinfunction "1_1") (pintype "passive"))
      (node (ref "U13") (pin "1") (pinfunction "OUT_1") (pintype "passive"))
    )
    (net (code "48") (name "Net-(U13A-–)") (class "Default")
      (node (ref "C101") (pin "2") (pinfunction "2_2") (pintype "passive"))
      (node (ref "R72") (pin "1") (pinfunction "1_1") (pintype "passive"))
      (node (ref "R74") (pin "2") (pinfunction "2_2") (pintype "passive"))
      (node (ref "U13") (pin "2") (pinfunction "–_2") (pintype "passive"))
    )
    (net (code "49") (name "Net-(U13B-+)") (class "Default")
      (node (ref "C111") (pin "2") (pinfunction "2_2") (pintype "passive"))
      (node (ref "R90") (pin "2") (pinfunction "2_2") (pintype "passive"))
      (node (ref "R94") (pin "1") (pinfunction "1_1") (pintype "passive"))
      (node (ref "U13") (pin "5") (pinfunction "+_5") (pintype "passive"))
    )
    (net (code "50") (name "Net-(U13B-OUT)") (class "Default")
      (node (ref "C107") (pin "1") (pinfunction "1_1") (pintype "passive"))
      (node (ref "R88") (pin "1") (pinfunction "1_1") (pintype "passive"))
      (node (ref "U13") (pin "7") (pinfunction "OUT_7") (pintype "passive"))
    )
    (net (code "51") (name "Net-(U13B-–)") (class "Default")
      (node (ref "C107") (pin "2") (pinfunction "2_2") (pintype "passive"))
      (node (ref "R84") (pin "1") (pinfunction "1_1") (pintype "passive"))
      (node (ref "R86") (pin "2") (pinfunction "2_2") (pintype "passive"))
      (node (ref "U13") (pin "6") (pinfunction "–_6") (pintype "passive"))
    )
  )
)
